# table4_vd1.net
KiCad netlist of a schematic drawn in EasyEDA
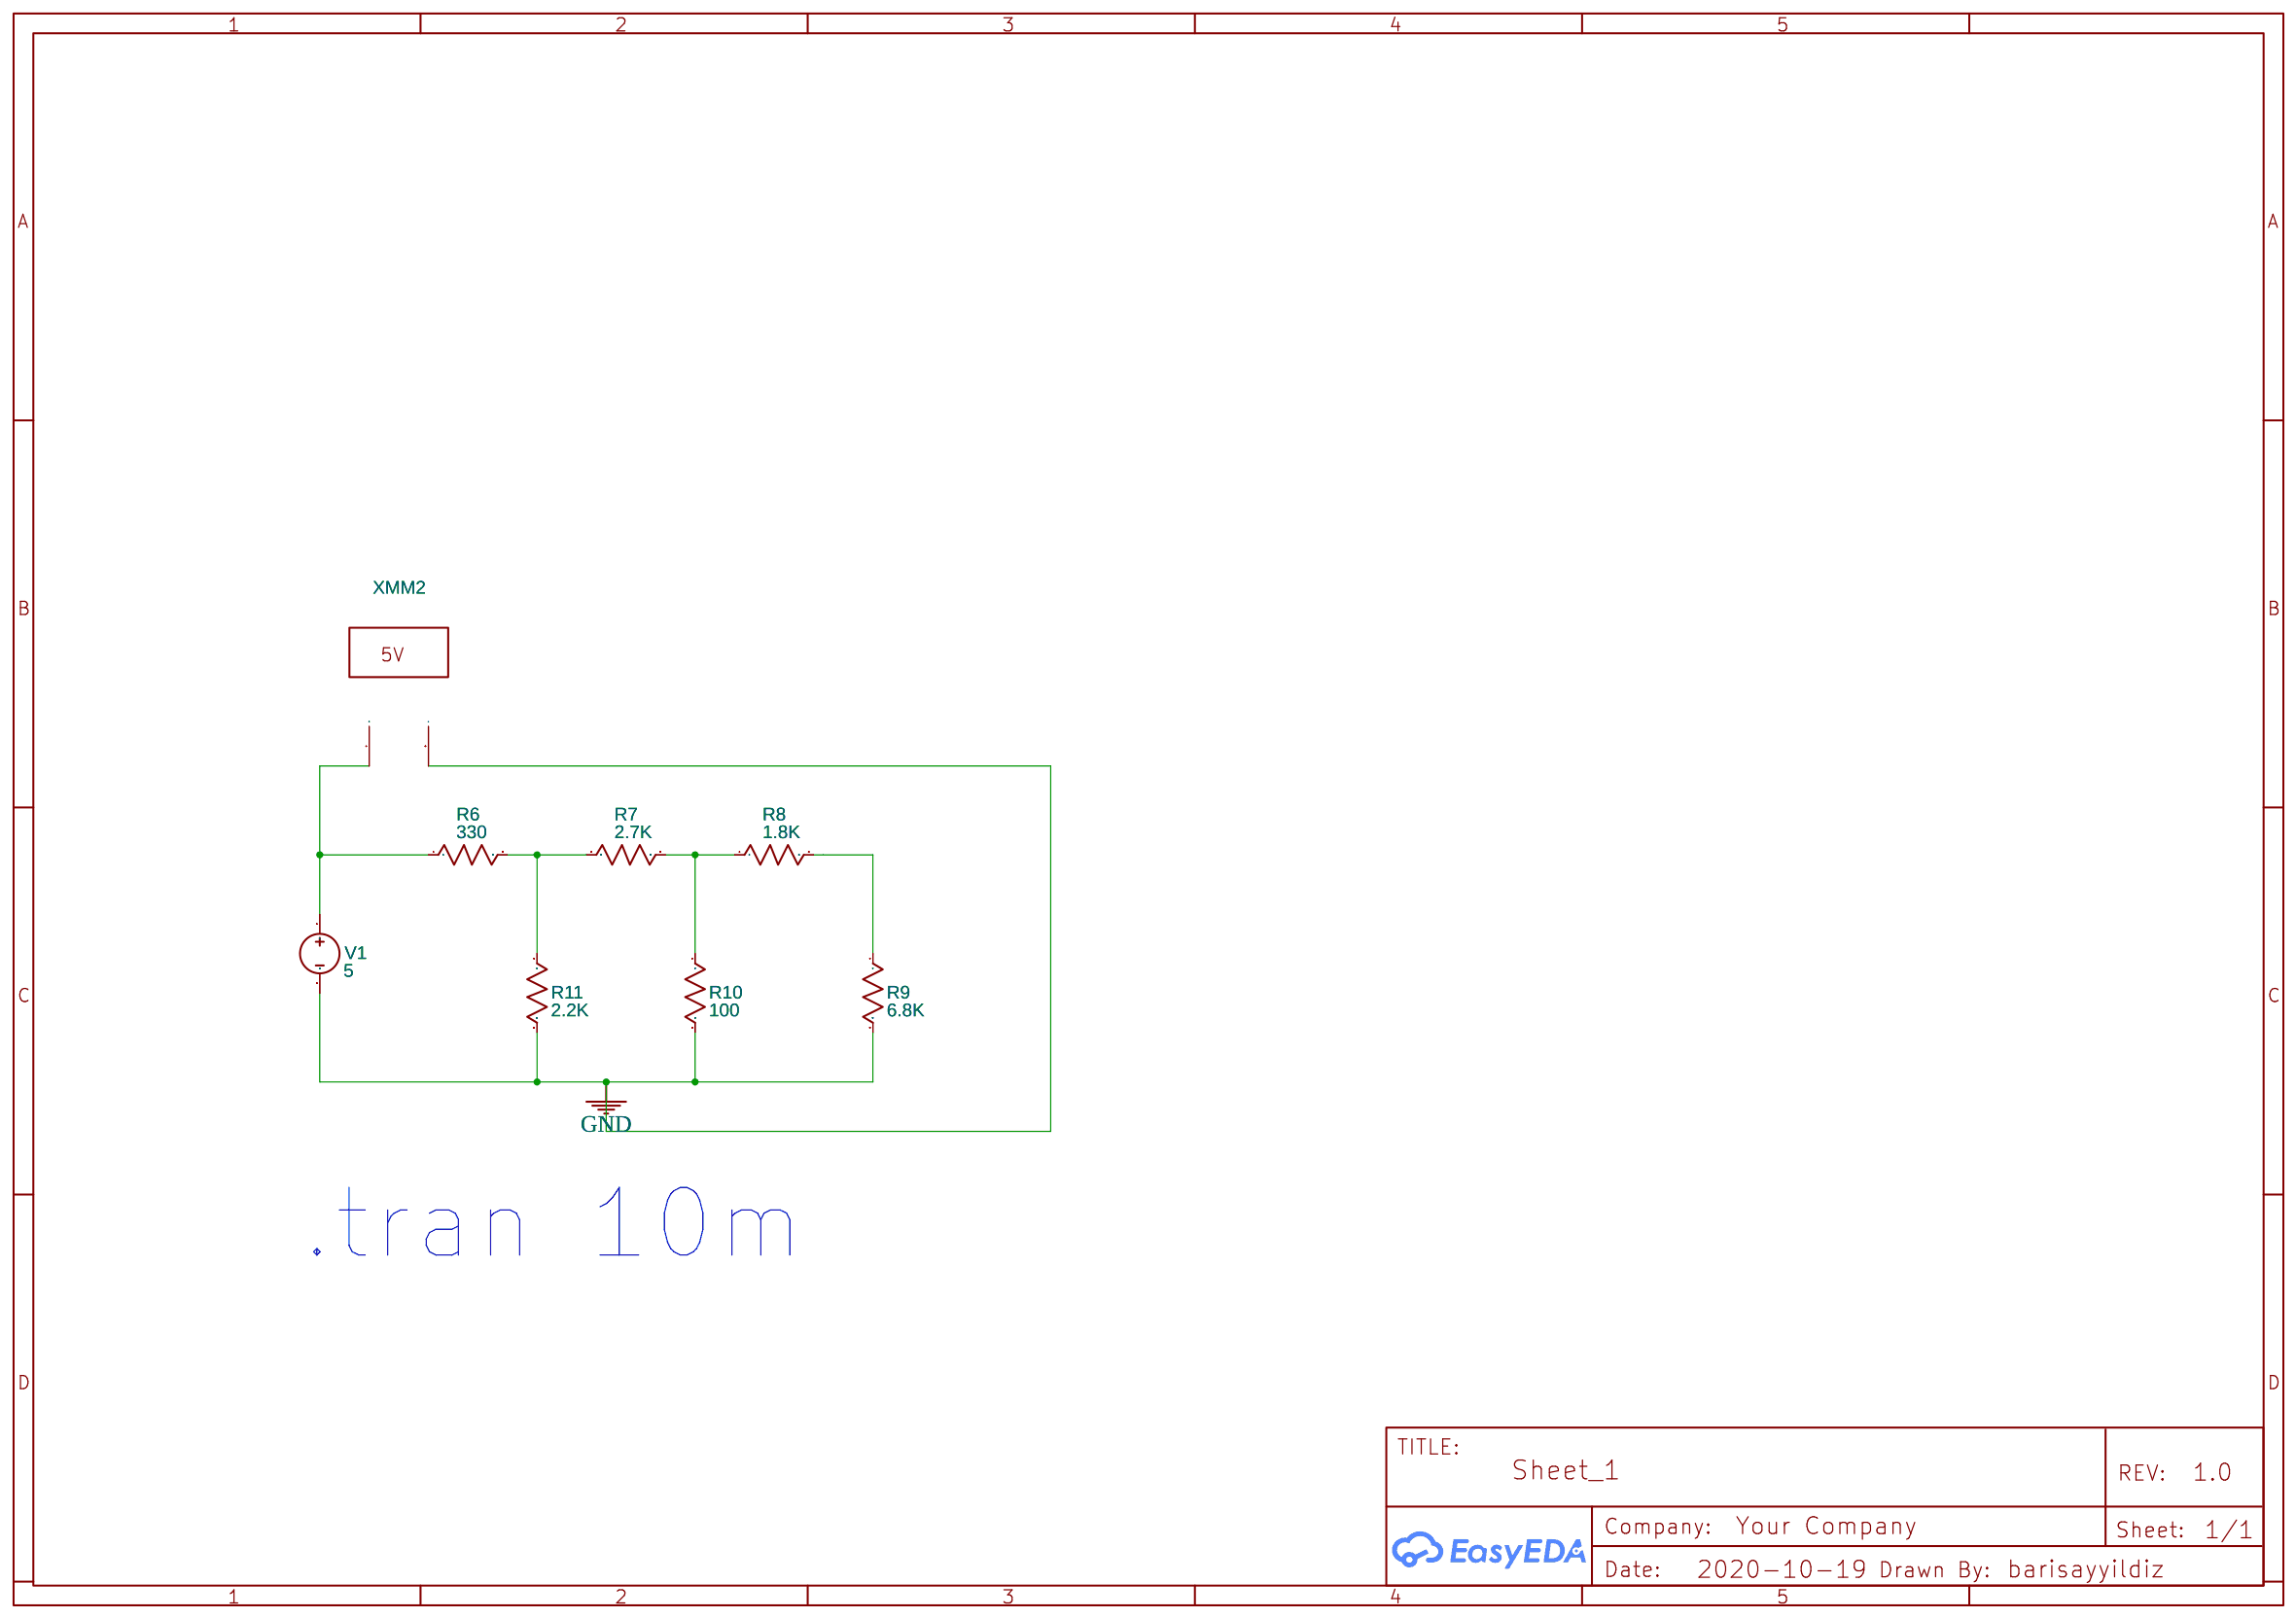
[diagram p0: schematic sheet]

(export (version "E")
  (design (tool "Eeschema 10.0.6"))
  (components
    (comp (ref "R6") (value "330") (libsource (lib "") (part "Resistor_US_1")))
    (comp (ref "R7") (value "2.7K") (libsource (lib "") (part "Resistor_US_1")))
    (comp (ref "R8") (value "1.8K") (libsource (lib "") (part "Resistor_US_1")))
    (comp (ref "R9") (value "6.8K") (libsource (lib "") (part "Resistor_US")))
    (comp (ref "R10") (value "100") (libsource (lib "") (part "Resistor_US")))
    (comp (ref "R11") (value "2.2K") (libsource (lib "") (part "Resistor_US")))
    (comp (ref "V1") (value "5") (libsource (lib "") (part "VDC")))
    (comp (ref "XMM2") (value "Multimeter") (libsource (lib "") (part "MULTIMETER")))
  )
  (nets
    (net (code "1") (name "GND") (class "Default")
      (node (ref "R10") (pin "2") (pinfunction "2_2") (pintype "unspecified"))
      (node (ref "R11") (pin "2") (pinfunction "2_2") (pintype "unspecified"))
      (node (ref "R9") (pin "2") (pinfunction "2_2") (pintype "unspecified"))
      (node (ref "V1") (pin "2") (pinfunction "2_2") (pintype "unspecified"))
      (node (ref "XMM2") (pin "2") (pinfunction "I_2") (pintype "unspecified"))
    )
    (net (code "2") (name "Net-(R8-Pad2)") (class "Default")
      (node (ref "R8") (pin "2") (pinfunction "2_2") (pintype "unspecified"))
      (node (ref "R9") (pin "1") (pinfunction "1_1") (pintype "unspecified"))
    )
    (net (code "3") (name "Net-(R10-Pad1)") (class "Default")
      (node (ref "R10") (pin "1") (pinfunction "1_1") (pintype "unspecified"))
      (node (ref "R7") (pin "2") (pinfunction "2_2") (pintype "unspecified"))
      (node (ref "R8") (pin "1") (pinfunction "1_1") (pintype "unspecified"))
    )
    (net (code "4") (name "Net-(R11-Pad1)") (class "Default")
      (node (ref "R11") (pin "1") (pinfunction "1_1") (pintype "unspecified"))
      (node (ref "R6") (pin "2") (pinfunction "2_2") (pintype "unspecified"))
      (node (ref "R7") (pin "1") (pinfunction "1_1") (pintype "unspecified"))
    )
    (net (code "5") (name "Net-(XMM2-+)") (class "Default")
      (node (ref "R6") (pin "1") (pinfunction "1_1") (pintype "unspecified"))
      (node (ref "V1") (pin "1") (pinfunction "1_1") (pintype "unspecified"))
      (node (ref "XMM2") (pin "1") (pinfunction "+_1") (pintype "unspecified"))
    )
  )
)
